# Main.net
KiCad netlist of a schematic drawn in Altium Designer
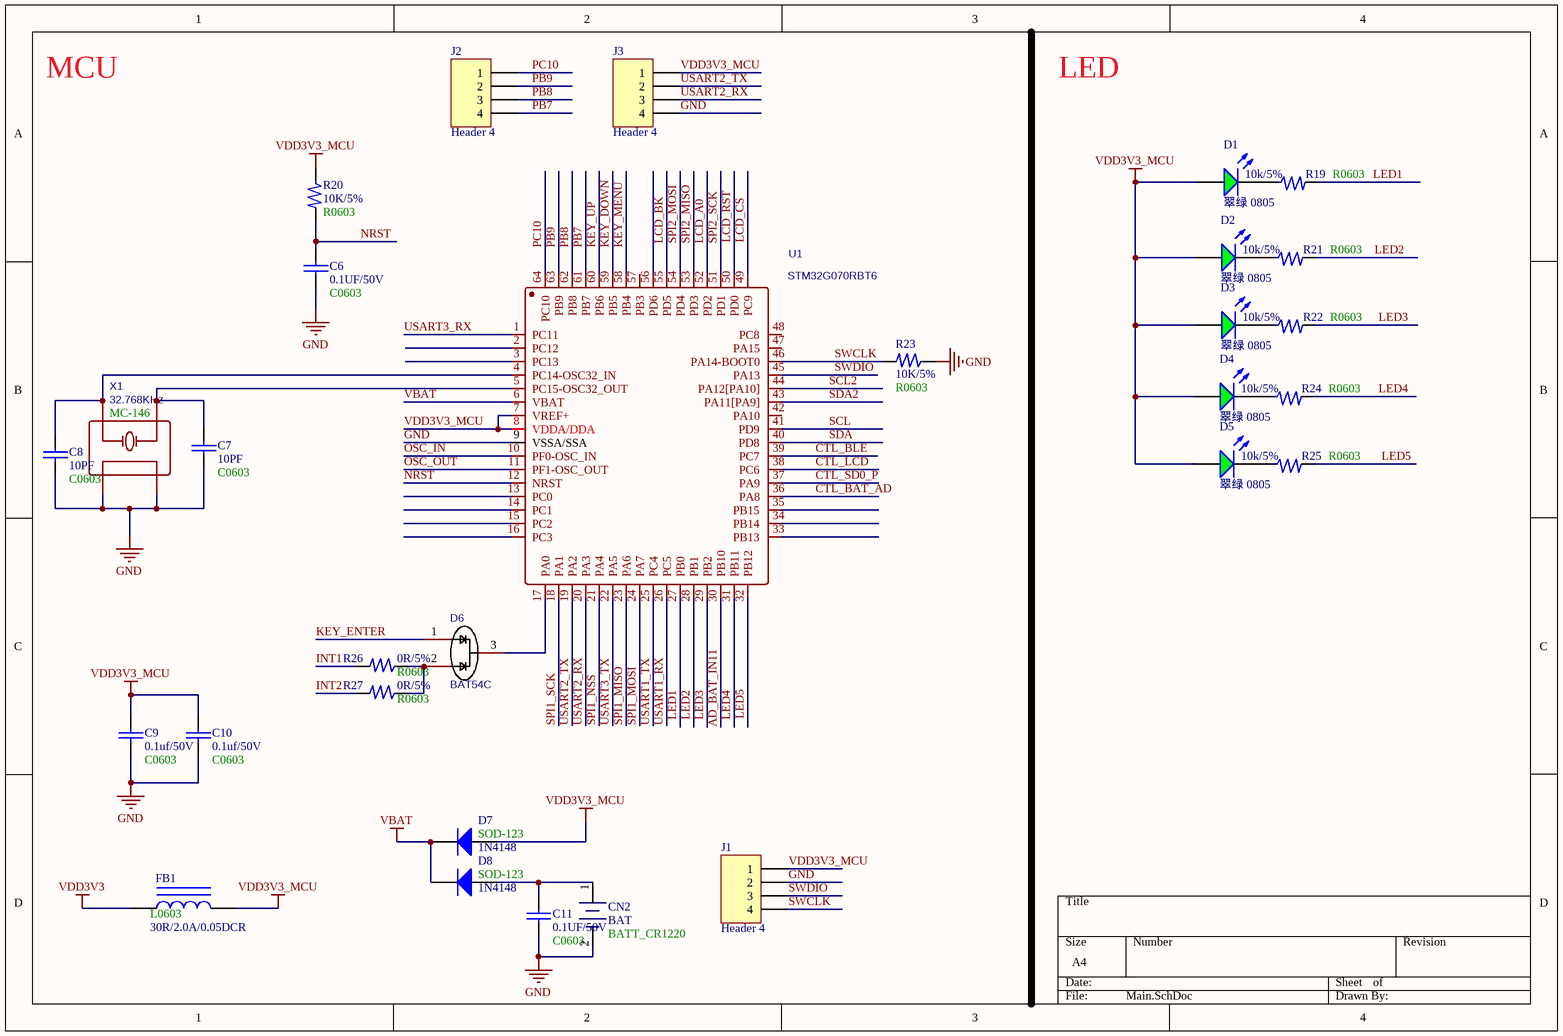
[diagram p0: Main.SchDoc]

(export (version "E")
  (design (tool "Eeschema 10.0.6"))
  (components
    (comp (ref "C6")
      (value "0.1UF/50V")
      (footprint "C0603")
      (description "Capacitor")
      (libsource (lib "*") (part "CAP"))
    )
    (comp (ref "C7")
      (value "10PF")
      (footprint "C0603")
      (description "Capacitor")
      (libsource (lib "*") (part "CAP"))
    )
    (comp (ref "C8")
      (value "10PF")
      (footprint "C0603")
      (description "Capacitor")
      (libsource (lib "*") (part "CAP"))
    )
    (comp (ref "C9")
      (value "0.1uf/50V")
      (footprint "C0603")
      (description "Capacitor")
      (libsource (lib "*") (part "CAP"))
    )
    (comp (ref "C10")
      (value "0.1uf/50V")
      (footprint "C0603")
      (description "Capacitor")
      (libsource (lib "*") (part "CAP"))
    )
    (comp (ref "C11")
      (value "0.1UF/50V")
      (footprint "C0603")
      (description "Capacitor")
      (libsource (lib "*") (part "CAP"))
    )
    (comp (ref "CN2") (value "BAT") (footprint "BATT_CR1220") (libsource (lib "M4") (part "BAT")))
    (comp (ref "D1")
      (value "翠绿 0805")
      (footprint "0805_LED_S1")
      (description "发光二极管")
      (libsource (lib "Miscellaneous Devices LC") (part "0805 翠绿"))
    )
    (comp (ref "D2")
      (value "翠绿 0805")
      (footprint "0805_LED_S1")
      (description "发光二极管")
      (libsource (lib "Miscellaneous Devices LC") (part "0805 翠绿"))
    )
    (comp (ref "D3")
      (value "翠绿 0805")
      (footprint "0805_LED_S1")
      (description "发光二极管")
      (libsource (lib "Miscellaneous Devices LC") (part "0805 翠绿"))
    )
    (comp (ref "D4")
      (value "翠绿 0805")
      (footprint "0805_LED_S1")
      (description "发光二极管")
      (libsource (lib "Miscellaneous Devices LC") (part "0805 翠绿"))
    )
    (comp (ref "D5")
      (value "翠绿 0805")
      (footprint "0805_LED_S1")
      (description "发光二极管")
      (libsource (lib "Miscellaneous Devices LC") (part "0805 翠绿"))
    )
    (comp (ref "D6")
      (value "BAT54C")
      (footprint "SOT-23(SOT-23-3)")
      (fields (field (name "MANUFACTURER") "CJ（江苏长电/长晶）") (field (name "MANUFACTURER PART") "BAT54CW"))
      (libsource (lib "altium-import") (part "root_3_BAT54CW_"))
    )
    (comp (ref "D7")
      (value "1N4148")
      (footprint "SOD-123")
      (description "肖特基二极管")
      (fields (field (name "PACKAGE") "SOD-123"))
      (libsource (lib "Miscellaneous Devices LC") (part "SOD-123 B5819W  SL"))
    )
    (comp (ref "D8")
      (value "1N4148")
      (footprint "SOD-123")
      (description "肖特基二极管")
      (fields (field (name "PACKAGE") "SOD-123"))
      (libsource (lib "Miscellaneous Devices LC") (part "SOD-123 B5819W  SL"))
    )
    (comp (ref "FB1")
      (value "30R/2.0A/0.05DCR")
      (footprint "0603_L")
      (description "贴片电感")
      (fields (field (name "PACKAGE") "L0603"))
      (libsource (lib "Miscellaneous Devices LC") (part "0603 3.9nH 0.3nH"))
    )
    (comp (ref "J1")
      (value "Header 4")
      (footprint "CON4-2.0")
      (description "Header, 4-Pin")
      (fields (field (name "PUBLISHER") "Altium Limited"))
      (libsource (lib "Miscellaneous Connectors") (part "Header 4"))
    )
    (comp (ref "J2")
      (value "Header 4")
      (footprint "HDR1X4")
      (description "Header, 4-Pin")
      (fields (field (name "PUBLISHER") "Altium Limited"))
      (libsource (lib "Miscellaneous Connectors") (part "Header 4"))
    )
    (comp (ref "J3")
      (value "Header 4")
      (footprint "HDR1X4")
      (description "Header, 4-Pin")
      (fields (field (name "PUBLISHER") "Altium Limited"))
      (libsource (lib "Miscellaneous Connectors") (part "Header 4"))
    )
    (comp (ref "R19") (value "10k/5%") (footprint "R0603") (libsource (lib "*") (part "电阻")))
    (comp (ref "R20") (value "10K/5%") (footprint "R0603") (libsource (lib "*") (part "电阻")))
    (comp (ref "R21") (value "10k/5%") (footprint "R0603") (libsource (lib "*") (part "电阻")))
    (comp (ref "R22") (value "10k/5%") (footprint "R0603") (libsource (lib "*") (part "电阻")))
    (comp (ref "R23") (value "10K/5%") (footprint "R0603") (libsource (lib "*") (part "电阻")))
    (comp (ref "R24") (value "10k/5%") (footprint "R0603") (libsource (lib "*") (part "电阻")))
    (comp (ref "R25") (value "10k/5%") (footprint "R0603") (libsource (lib "*") (part "电阻")))
    (comp (ref "R26") (value "0R/5%") (footprint "R0603") (libsource (lib "*") (part "电阻")))
    (comp (ref "R27") (value "0R/5%") (footprint "R0603") (libsource (lib "*") (part "电阻")))
    (comp (ref "U1")
      (value "STM32G070RBT6")
      (footprint "LQFP-64_L10.0-W10.0-P0.50-LS12.0-BL")
      (fields (field (name "BOM_SUPPLIER PART") "C529340") (field (name "CONTRIBUTOR") "LCSC"))
      (libsource (lib "altium-import") (part "root_0_STM32G070RBT6_"))
    )
    (comp (ref "X1")
      (value "32.768KHz")
      (footprint "MC-146_4P")
      (fields
        (field (name "BOM_MANUFACTURER PART") "MC-14632.768kHz7.0pF20PPM")
        (field (name "BOM_SUPPLIER PART") "C94977")
        (field (name "ALTIUM_UNNAMED_1") "MC-146")
        (field (name "CONTRIBUTOR") "LCSC")
      )
      (libsource (lib "altium-import") (part "root_3_32.768KHz_"))
    )
  )
  (nets
    (net (code "1") (name "/AD_BAT_IN11") (class "Default")
      (node (ref "U1") (pin "30") (pinfunction "PB10_30") (pintype "passive"))
    )
    (net (code "2") (name "/CTL_BAT_AD") (class "Default")
      (node (ref "U1") (pin "36") (pinfunction "PA8_36") (pintype "passive"))
    )
    (net (code "3") (name "/CTL_BLE") (class "Default")
      (node (ref "U1") (pin "39") (pinfunction "PC7_39") (pintype "passive"))
    )
    (net (code "4") (name "/CTL_LCD") (class "Default")
      (node (ref "U1") (pin "38") (pinfunction "PC6_38") (pintype "passive"))
    )
    (net (code "5") (name "/CTL_SD0_P") (class "Default")
      (node (ref "U1") (pin "37") (pinfunction "PA9_37") (pintype "passive"))
    )
    (net (code "6") (name "/INT1") (class "Default") (node (ref "R26") (pin "1") (pintype "passive")))
    (net (code "7") (name "/INT2") (class "Default") (node (ref "R27") (pin "1") (pintype "passive")))
    (net (code "8") (name "/KEY_DOWN") (class "Default")
      (node (ref "U1") (pin "59") (pinfunction "PB5_59") (pintype "passive"))
    )
    (net (code "9") (name "/KEY_ENTER") (class "Default")
      (node (ref "D6") (pin "1") (pinfunction "1_1") (pintype "passive"))
    )
    (net (code "10") (name "/KEY_MENU") (class "Default")
      (node (ref "U1") (pin "58") (pinfunction "PB4_58") (pintype "passive"))
    )
    (net (code "11") (name "/KEY_UP") (class "Default")
      (node (ref "U1") (pin "60") (pinfunction "PB6_60") (pintype "passive"))
    )
    (net (code "12") (name "/LCD_A0") (class "Default")
      (node (ref "U1") (pin "52") (pinfunction "PD2_52") (pintype "passive"))
    )
    (net (code "13") (name "/LCD_BK") (class "Default")
      (node (ref "U1") (pin "55") (pinfunction "PD5_55") (pintype "passive"))
    )
    (net (code "14") (name "/LCD_CS") (class "Default")
      (node (ref "U1") (pin "49") (pinfunction "PC9_49") (pintype "passive"))
    )
    (net (code "15") (name "/LCD_RST") (class "Default")
      (node (ref "U1") (pin "50") (pinfunction "PD0_50") (pintype "passive"))
    )
    (net (code "16") (name "/LED1") (class "Default")
      (node (ref "R19") (pin "1") (pintype "passive"))
      (node (ref "U1") (pin "27") (pinfunction "PB0_27") (pintype "passive"))
    )
    (net (code "17") (name "/LED2") (class "Default")
      (node (ref "R21") (pin "1") (pintype "passive"))
      (node (ref "U1") (pin "28") (pinfunction "PB1_28") (pintype "passive"))
    )
    (net (code "18") (name "/LED3") (class "Default")
      (node (ref "R22") (pin "1") (pintype "passive"))
      (node (ref "U1") (pin "29") (pinfunction "PB2_29") (pintype "passive"))
    )
    (net (code "19") (name "/LED4") (class "Default")
      (node (ref "R24") (pin "1") (pintype "passive"))
      (node (ref "U1") (pin "31") (pinfunction "PB11_31") (pintype "passive"))
    )
    (net (code "20") (name "/LED5") (class "Default")
      (node (ref "R25") (pin "1") (pintype "passive"))
      (node (ref "U1") (pin "32") (pinfunction "PB12_32") (pintype "passive"))
    )
    (net (code "21") (name "/NRST") (class "Default")
      (node (ref "C6") (pin "2") (pinfunction "2_2") (pintype "passive"))
      (node (ref "R20") (pin "1") (pintype "passive"))
      (node (ref "U1") (pin "12") (pinfunction "NRST_12") (pintype "passive"))
    )
    (net (code "22") (name "/OSC_IN") (class "Default")
      (node (ref "U1") (pin "10") (pinfunction "PF0-OSC_IN_10") (pintype "passive"))
    )
    (net (code "23") (name "/OSC_OUT") (class "Default")
      (node (ref "U1") (pin "11") (pinfunction "PF1-OSC_OUT_11") (pintype "passive"))
    )
    (net (code "24") (name "/PB7") (class "Default")
      (node (ref "J2") (pin "4") (pinfunction "4_4") (pintype "passive"))
      (node (ref "U1") (pin "61") (pinfunction "PB7_61") (pintype "passive"))
    )
    (net (code "25") (name "/PB8") (class "Default")
      (node (ref "J2") (pin "3") (pinfunction "3_3") (pintype "passive"))
      (node (ref "U1") (pin "62") (pinfunction "PB8_62") (pintype "passive"))
    )
    (net (code "26") (name "/PB9") (class "Default")
      (node (ref "J2") (pin "2") (pinfunction "2_2") (pintype "passive"))
      (node (ref "U1") (pin "63") (pinfunction "PB9_63") (pintype "passive"))
    )
    (net (code "27") (name "/PC10") (class "Default")
      (node (ref "J2") (pin "1") (pinfunction "1_1") (pintype "passive"))
      (node (ref "U1") (pin "64") (pinfunction "PC10_64") (pintype "passive"))
    )
    (net (code "28") (name "/SCL") (class "Default")
      (node (ref "U1") (pin "41") (pinfunction "PD9_41") (pintype "passive"))
    )
    (net (code "29") (name "/SCL2") (class "Default")
      (node (ref "U1") (pin "44") (pinfunction "PA12[PA10]_44") (pintype "passive"))
    )
    (net (code "30") (name "/SDA") (class "Default")
      (node (ref "U1") (pin "40") (pinfunction "PD8_40") (pintype "passive"))
    )
    (net (code "31") (name "/SDA2") (class "Default")
      (node (ref "U1") (pin "43") (pinfunction "PA11[PA9]_43") (pintype "passive"))
    )
    (net (code "32") (name "/SPI1_MISO") (class "Default")
      (node (ref "U1") (pin "23") (pinfunction "PA6_23") (pintype "passive"))
    )
    (net (code "33") (name "/SPI1_MOSI") (class "Default")
      (node (ref "U1") (pin "24") (pinfunction "PA7_24") (pintype "passive"))
    )
    (net (code "34") (name "/SPI1_NSS") (class "Default")
      (node (ref "U1") (pin "21") (pinfunction "PA4_21") (pintype "passive"))
    )
    (net (code "35") (name "/SPI1_SCK") (class "Default")
      (node (ref "U1") (pin "18") (pinfunction "PA1_18") (pintype "passive"))
    )
    (net (code "36") (name "/SPI2_MISO") (class "Default")
      (node (ref "U1") (pin "53") (pinfunction "PD3_53") (pintype "passive"))
    )
    (net (code "37") (name "/SPI2_MOSI") (class "Default")
      (node (ref "U1") (pin "54") (pinfunction "PD4_54") (pintype "passive"))
    )
    (net (code "38") (name "/SPI2_SCK") (class "Default")
      (node (ref "U1") (pin "51") (pinfunction "PD1_51") (pintype "passive"))
    )
    (net (code "39") (name "/SWCLK") (class "Default")
      (node (ref "J1") (pin "4") (pinfunction "4_4") (pintype "passive"))
      (node (ref "R23") (pin "1") (pintype "passive"))
      (node (ref "U1") (pin "46") (pinfunction "PA14-BOOT0_46") (pintype "passive"))
    )
    (net (code "40") (name "/SWDIO") (class "Default")
      (node (ref "J1") (pin "3") (pinfunction "3_3") (pintype "passive"))
      (node (ref "U1") (pin "45") (pinfunction "PA13_45") (pintype "passive"))
    )
    (net (code "41") (name "/USART1_RX") (class "Default")
      (node (ref "U1") (pin "26") (pinfunction "PC5_26") (pintype "passive"))
    )
    (net (code "42") (name "/USART1_TX") (class "Default")
      (node (ref "U1") (pin "25") (pinfunction "PC4_25") (pintype "passive"))
    )
    (net (code "43") (name "/USART2_RX") (class "Default")
      (node (ref "J3") (pin "3") (pinfunction "3_3") (pintype "passive"))
      (node (ref "U1") (pin "20") (pinfunction "PA3_20") (pintype "passive"))
    )
    (net (code "44") (name "/USART2_TX") (class "Default")
      (node (ref "J3") (pin "2") (pinfunction "2_2") (pintype "passive"))
      (node (ref "U1") (pin "19") (pinfunction "PA2_19") (pintype "passive"))
    )
    (net (code "45") (name "/USART3_RX") (class "Default")
      (node (ref "U1") (pin "1") (pinfunction "PC11_1") (pintype "passive"))
    )
    (net (code "46") (name "/USART3_TX") (class "Default")
      (node (ref "U1") (pin "22") (pinfunction "PA5_22") (pintype "passive"))
    )
    (net (code "47") (name "GND") (class "Default")
      (node (ref "C10") (pin "2") (pinfunction "2_2") (pintype "passive"))
      (node (ref "C11") (pin "1") (pinfunction "1_1") (pintype "passive"))
      (node (ref "C6") (pin "1") (pinfunction "1_1") (pintype "passive"))
      (node (ref "C7") (pin "2") (pinfunction "2_2") (pintype "passive"))
      (node (ref "C8") (pin "2") (pinfunction "2_2") (pintype "passive"))
      (node (ref "C9") (pin "2") (pinfunction "2_2") (pintype "passive"))
      (node (ref "CN2") (pin "2") (pintype "passive"))
      (node (ref "J1") (pin "2") (pinfunction "2_2") (pintype "passive"))
      (node (ref "J3") (pin "4") (pinfunction "4_4") (pintype "passive"))
      (node (ref "R23") (pin "2") (pintype "passive"))
      (node (ref "U1") (pin "9") (pinfunction "VSSA/SSA_9") (pintype "passive"))
      (node (ref "X1") (pin "2") (pinfunction "2_2") (pintype "passive"))
      (node (ref "X1") (pin "3") (pinfunction "3_3") (pintype "passive"))
    )
    (net (code "48") (name "Net-(D1-PadK)") (class "Default")
      (node (ref "D1") (pin "K") (pinfunction "K_K") (pintype "passive"))
      (node (ref "R19") (pin "2") (pintype "passive"))
    )
    (net (code "49") (name "Net-(D2-PadK)") (class "Default")
      (node (ref "D2") (pin "K") (pinfunction "K_K") (pintype "passive"))
      (node (ref "R21") (pin "2") (pintype "passive"))
    )
    (net (code "50") (name "Net-(D3-PadK)") (class "Default")
      (node (ref "D3") (pin "K") (pinfunction "K_K") (pintype "passive"))
      (node (ref "R22") (pin "2") (pintype "passive"))
    )
    (net (code "51") (name "Net-(D4-PadK)") (class "Default")
      (node (ref "D4") (pin "K") (pinfunction "K_K") (pintype "passive"))
      (node (ref "R24") (pin "2") (pintype "passive"))
    )
    (net (code "52") (name "Net-(D5-PadK)") (class "Default")
      (node (ref "D5") (pin "K") (pinfunction "K_K") (pintype "passive"))
      (node (ref "R25") (pin "2") (pintype "passive"))
    )
    (net (code "53") (name "Net-(D6-Pad2)") (class "Default")
      (node (ref "D6") (pin "2") (pinfunction "2_2") (pintype "passive"))
      (node (ref "R26") (pin "2") (pintype "passive"))
      (node (ref "R27") (pin "2") (pintype "passive"))
    )
    (net (code "54") (name "Net-(D8-A)") (class "Default")
      (node (ref "C11") (pin "2") (pinfunction "2_2") (pintype "passive"))
      (node (ref "CN2") (pin "1") (pintype "passive"))
      (node (ref "D8") (pin "1") (pinfunction "A_1") (pintype "passive"))
    )
    (net (code "55") (name "Net-(U1-PA0)") (class "Default")
      (node (ref "D6") (pin "3") (pinfunction "3_3") (pintype "passive"))
      (node (ref "U1") (pin "17") (pinfunction "PA0_17") (pintype "passive"))
    )
    (net (code "56") (name "Net-(U1-PC14-OSC32_IN)") (class "Default")
      (node (ref "C8") (pin "1") (pinfunction "1_1") (pintype "passive"))
      (node (ref "U1") (pin "4") (pinfunction "PC14-OSC32_IN_4") (pintype "passive"))
      (node (ref "X1") (pin "1") (pinfunction "OSC1_1") (pintype "passive"))
    )
    (net (code "57") (name "Net-(U1-PC15-OSC32_OUT)") (class "Default")
      (node (ref "C7") (pin "1") (pinfunction "1_1") (pintype "passive"))
      (node (ref "U1") (pin "5") (pinfunction "PC15-OSC32_OUT_5") (pintype "passive"))
      (node (ref "X1") (pin "4") (pinfunction "OSC2_4") (pintype "passive"))
    )
    (net (code "58") (name "VBAT") (class "Default")
      (node (ref "D7") (pin "2") (pinfunction "K_2") (pintype "passive"))
      (node (ref "D8") (pin "2") (pinfunction "K_2") (pintype "passive"))
      (node (ref "U1") (pin "6") (pinfunction "VBAT_6") (pintype "passive"))
    )
    (net (code "59") (name "VDD3V3") (class "Default")
      (node (ref "FB1") (pin "1") (pinfunction "1_1") (pintype "passive"))
    )
    (net (code "60") (name "VDD3V3_MCU") (class "Default")
      (node (ref "C10") (pin "1") (pinfunction "1_1") (pintype "passive"))
      (node (ref "C9") (pin "1") (pinfunction "1_1") (pintype "passive"))
      (node (ref "D1") (pin "A") (pinfunction "A_A") (pintype "passive"))
      (node (ref "D2") (pin "A") (pinfunction "A_A") (pintype "passive"))
      (node (ref "D3") (pin "A") (pinfunction "A_A") (pintype "passive"))
      (node (ref "D4") (pin "A") (pinfunction "A_A") (pintype "passive"))
      (node (ref "D5") (pin "A") (pinfunction "A_A") (pintype "passive"))
      (node (ref "D7") (pin "1") (pinfunction "A_1") (pintype "passive"))
      (node (ref "FB1") (pin "2") (pinfunction "2_2") (pintype "passive"))
      (node (ref "J1") (pin "1") (pinfunction "1_1") (pintype "passive"))
      (node (ref "J3") (pin "1") (pinfunction "1_1") (pintype "passive"))
      (node (ref "R20") (pin "2") (pintype "passive"))
      (node (ref "U1") (pin "7") (pinfunction "VREF+_7") (pintype "passive"))
      (node (ref "U1") (pin "8") (pinfunction "VDDA/DDA_8") (pintype "passive"))
    )
    (net (code "61") (name "unconnected-(U1-PA10-Pad42)") (class "Default")
      (node (ref "U1") (pin "42") (pinfunction "PA10_42") (pintype "passive"))
    )
    (net (code "62") (name "unconnected-(U1-PA15-Pad47)") (class "Default")
      (node (ref "U1") (pin "47") (pinfunction "PA15_47") (pintype "passive"))
    )
    (net (code "63") (name "unconnected-(U1-PB3-Pad57)") (class "Default")
      (node (ref "U1") (pin "57") (pinfunction "PB3_57") (pintype "passive"))
    )
    (net (code "64") (name "unconnected-(U1-PB13-Pad33)") (class "Default")
      (node (ref "U1") (pin "33") (pinfunction "PB13_33") (pintype "passive"))
    )
    (net (code "65") (name "unconnected-(U1-PB14-Pad34)") (class "Default")
      (node (ref "U1") (pin "34") (pinfunction "PB14_34") (pintype "passive"))
    )
    (net (code "66") (name "unconnected-(U1-PB15-Pad35)") (class "Default")
      (node (ref "U1") (pin "35") (pinfunction "PB15_35") (pintype "passive"))
    )
    (net (code "67") (name "unconnected-(U1-PC0-Pad13)") (class "Default")
      (node (ref "U1") (pin "13") (pinfunction "PC0_13") (pintype "passive"))
    )
    (net (code "68") (name "unconnected-(U1-PC1-Pad14)") (class "Default")
      (node (ref "U1") (pin "14") (pinfunction "PC1_14") (pintype "passive"))
    )
    (net (code "69") (name "unconnected-(U1-PC2-Pad15)") (class "Default")
      (node (ref "U1") (pin "15") (pinfunction "PC2_15") (pintype "passive"))
    )
    (net (code "70") (name "unconnected-(U1-PC3-Pad16)") (class "Default")
      (node (ref "U1") (pin "16") (pinfunction "PC3_16") (pintype "passive"))
    )
    (net (code "71") (name "unconnected-(U1-PC8-Pad48)") (class "Default")
      (node (ref "U1") (pin "48") (pinfunction "PC8_48") (pintype "passive"))
    )
    (net (code "72") (name "unconnected-(U1-PC12-Pad2)") (class "Default")
      (node (ref "U1") (pin "2") (pinfunction "PC12_2") (pintype "passive"))
    )
    (net (code "73") (name "unconnected-(U1-PC13-Pad3)") (class "Default")
      (node (ref "U1") (pin "3") (pinfunction "PC13_3") (pintype "passive"))
    )
    (net (code "74") (name "unconnected-(U1-PD6-Pad56)") (class "Default")
      (node (ref "U1") (pin "56") (pinfunction "PD6_56") (pintype "passive"))
    )
  )
)
